# DRV8833_Dev.net
KiCad netlist of a schematic drawn in Altium Designer
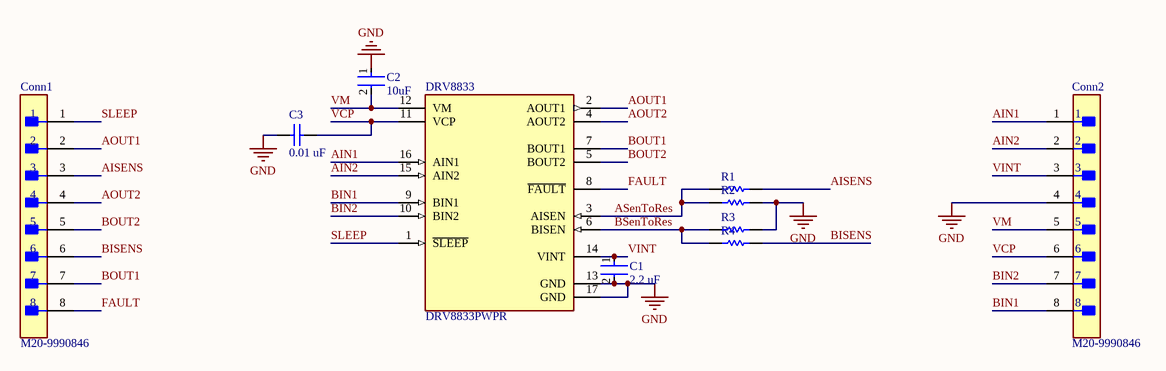
[diagram p0: DRV8833_Dev.SchDoc]

(export (version "E")
  (design (tool "Eeschema 10.0.6"))
  (components
    (comp (ref "C1")
      (value "2.2 uF")
      (footprint "FP-GRM188-0_1-e0_2_0_5-MFG")
      (description "Chip Multilayer Ceramic Capacitors for General Purpose, 0603, 2.2uF, X7R, 15%, 10%, 10V")
      (fields (field (name "VOLTAGE") "10V") (field (name "TOLERANCE") "10%"))
      (libsource (lib "Altium Content Vault") (part "11868f565c42a9108669ba33697ecf6"))
    )
    (comp (ref "C2")
      (value "10uF")
      (footprint "FP-GRM188-0_1-e0_2_0_55-IPC_A")
      (description "Chip Multilayer Ceramic Capacitors for General Purpose, 0603, 10uF, X5R, 15%, 20%, 6.3V")
      (fields (field (name "VOLTAGE") "6.3V") (field (name "TOLERANCE") "20%"))
      (libsource (lib "Altium Content Vault") (part "02cd4be3c70576c341d710602a673aa"))
    )
    (comp (ref "C3")
      (value "0.01 uF")
      (footprint "CAPC1608X90X35ML10T15")
      (description "Chip Capacitor, 10 nF, +/- 10%, 50 V, -55 to 125 degC, 0603 (1608 Metric), RoHS, Tape and Reel")
      (fields (field (name "VOLTAGE") "50V") (field (name "TOLERANCE") "10%"))
      (libsource (lib "Altium Content Vault") (part "CAP-NP-2"))
    )
    (comp (ref "Conn1")
      (value "M20-9990846")
      (footprint "FP-M20-9990846-MFG")
      (description "CONN HEADER VERT 8POS 2.54MM")
      (libsource (lib "") (part "99ec2b232beb5d2356d4d77f6a047f0_1"))
    )
    (comp (ref "Conn2")
      (value "M20-9990846")
      (footprint "FP-M20-9990846-MFG")
      (description "CONN HEADER VERT 8POS 2.54MM")
      (libsource (lib "Altium Content Vault") (part "99ec2b232beb5d2356d4d77f6a047f0"))
    )
    (comp (ref "DRV8833")
      (value "DRV8833PWPR")
      (footprint "FP-PWP0016C-IPC_B")
      (description "IC MOTOR DRIVER PAR 16HTSSOP")
      (libsource (lib "Altium Content Vault") (part "bca689d78e207bdabf30b9b31c2f798"))
    )
    (comp (ref "R1")
      (value "~")
      (footprint "RESC1609X50X30NL10T20")
      (fields (field (name "MANUFACTURER") "Vishay Dale") (field (name "PART NUMBER") "CRCW06031R00FKEA"))
      (libsource (lib "Altium Content Vault") (part "RES"))
    )
    (comp (ref "R2")
      (value "~")
      (footprint "RESC1608X55X25ML10T15")
      (description "Chip Resistor, 0 Ohm, +/- 5%, 0.1 W, -55 to 155 degC, 0603 (1608 Metric), RoHS, Tape and Reel")
      (fields (field (name "TOLERANCE") "5%") (field (name "MANUFACTURER") "Yageo"))
      (libsource (lib "Altium Content Vault") (part "RES-2"))
    )
    (comp (ref "R3")
      (value "~")
      (footprint "RESC1608X55X25ML10T15")
      (description "Chip Resistor, 0 Ohm, +/- 5%, 0.1 W, -55 to 155 degC, 0603 (1608 Metric), RoHS, Tape and Reel")
      (fields (field (name "TOLERANCE") "5%") (field (name "MANUFACTURER") "Yageo"))
      (libsource (lib "Altium Content Vault") (part "RES-2"))
    )
    (comp (ref "R4")
      (value "~")
      (footprint "RESC1609X50X30NL10T20")
      (fields (field (name "MANUFACTURER") "Vishay Dale") (field (name "PART NUMBER") "CRCW06031R00FKEA"))
      (libsource (lib "Altium Content Vault") (part "RES"))
    )
  )
  (nets
    (net (code "1") (name "/AIN1") (class "Default")
      (node (ref "Conn2") (pin "1") (pinfunction "1_1") (pintype "passive"))
      (node (ref "DRV8833") (pin "16") (pinfunction "AIN1_16") (pintype "input"))
    )
    (net (code "2") (name "/AIN2") (class "Default")
      (node (ref "Conn2") (pin "2") (pinfunction "2_2") (pintype "passive"))
      (node (ref "DRV8833") (pin "15") (pinfunction "AIN2_15") (pintype "input"))
    )
    (net (code "3") (name "/AISENS") (class "Default")
      (node (ref "Conn1") (pin "3") (pinfunction "3_3") (pintype "passive"))
      (node (ref "R1") (pin "2") (pinfunction "2_2") (pintype "passive"))
    )
    (net (code "4") (name "/AOUT1") (class "Default")
      (node (ref "Conn1") (pin "2") (pinfunction "2_2") (pintype "passive"))
      (node (ref "DRV8833") (pin "2") (pinfunction "AOUT1_2") (pintype "output"))
    )
    (net (code "5") (name "/AOUT2") (class "Default")
      (node (ref "Conn1") (pin "4") (pinfunction "4_4") (pintype "passive"))
      (node (ref "DRV8833") (pin "4") (pinfunction "AOUT2_4") (pintype "tri_state"))
    )
    (net (code "6") (name "/ASenToRes") (class "Default")
      (node (ref "DRV8833") (pin "3") (pinfunction "AISEN_3") (pintype "input"))
      (node (ref "R1") (pin "1") (pinfunction "1_1") (pintype "passive"))
      (node (ref "R2") (pin "1") (pinfunction "1_1") (pintype "passive"))
    )
    (net (code "7") (name "/BIN1") (class "Default")
      (node (ref "Conn2") (pin "8") (pinfunction "8_8") (pintype "passive"))
      (node (ref "DRV8833") (pin "9") (pinfunction "BIN1_9") (pintype "input"))
    )
    (net (code "8") (name "/BIN2") (class "Default")
      (node (ref "Conn2") (pin "7") (pinfunction "7_7") (pintype "passive"))
      (node (ref "DRV8833") (pin "10") (pinfunction "BIN2_10") (pintype "input"))
    )
    (net (code "9") (name "/BISENS") (class "Default")
      (node (ref "Conn1") (pin "6") (pinfunction "6_6") (pintype "passive"))
      (node (ref "R4") (pin "2") (pinfunction "2_2") (pintype "passive"))
    )
    (net (code "10") (name "/BOUT1") (class "Default")
      (node (ref "Conn1") (pin "7") (pinfunction "7_7") (pintype "passive"))
      (node (ref "DRV8833") (pin "7") (pinfunction "BOUT1_7") (pintype "tri_state"))
    )
    (net (code "11") (name "/BOUT2") (class "Default")
      (node (ref "Conn1") (pin "5") (pinfunction "5_5") (pintype "passive"))
      (node (ref "DRV8833") (pin "5") (pinfunction "BOUT2_5") (pintype "tri_state"))
    )
    (net (code "12") (name "/BSenToRes") (class "Default")
      (node (ref "DRV8833") (pin "6") (pinfunction "BISEN_6") (pintype "input"))
      (node (ref "R3") (pin "1") (pinfunction "1_1") (pintype "passive"))
      (node (ref "R4") (pin "1") (pinfunction "1_1") (pintype "passive"))
    )
    (net (code "13") (name "/FAULT") (class "Default")
      (node (ref "Conn1") (pin "8") (pinfunction "8_8") (pintype "passive"))
      (node (ref "DRV8833") (pin "8") (pinfunction "~{FAULT}_8") (pintype "open_collector"))
    )
    (net (code "14") (name "/SLEEP") (class "Default")
      (node (ref "Conn1") (pin "1") (pinfunction "1_1") (pintype "passive"))
      (node (ref "DRV8833") (pin "1") (pinfunction "~{SLEEP}_1") (pintype "input"))
    )
    (net (code "15") (name "/VCP") (class "Default")
      (node (ref "C3") (pin "2") (pinfunction "2_2") (pintype "passive"))
      (node (ref "Conn2") (pin "6") (pinfunction "6_6") (pintype "passive"))
      (node (ref "DRV8833") (pin "11") (pinfunction "VCP_11") (pintype "passive"))
    )
    (net (code "16") (name "/VINT") (class "Default")
      (node (ref "C1") (pin "1") (pinfunction "1_1") (pintype "passive"))
      (node (ref "Conn2") (pin "3") (pinfunction "3_3") (pintype "passive"))
      (node (ref "DRV8833") (pin "14") (pinfunction "VINT_14") (pintype "power_in"))
    )
    (net (code "17") (name "/VM") (class "Default")
      (node (ref "C2") (pin "2") (pinfunction "2_2") (pintype "passive"))
      (node (ref "Conn2") (pin "5") (pinfunction "5_5") (pintype "passive"))
      (node (ref "DRV8833") (pin "12") (pinfunction "VM_12") (pintype "power_in"))
    )
    (net (code "18") (name "GND") (class "Default")
      (node (ref "C1") (pin "2") (pinfunction "2_2") (pintype "passive"))
      (node (ref "C2") (pin "1") (pinfunction "1_1") (pintype "passive"))
      (node (ref "C3") (pin "1") (pinfunction "1_1") (pintype "passive"))
      (node (ref "Conn2") (pin "4") (pinfunction "4_4") (pintype "passive"))
      (node (ref "DRV8833") (pin "13") (pinfunction "GND_13") (pintype "power_in"))
      (node (ref "DRV8833") (pin "17") (pinfunction "GND_17") (pintype "power_in"))
      (node (ref "R2") (pin "2") (pinfunction "2_2") (pintype "passive"))
      (node (ref "R3") (pin "2") (pinfunction "2_2") (pintype "passive"))
    )
  )
)
